# led_4x6_board.net
KiCad netlist of a schematic drawn in EAGLE
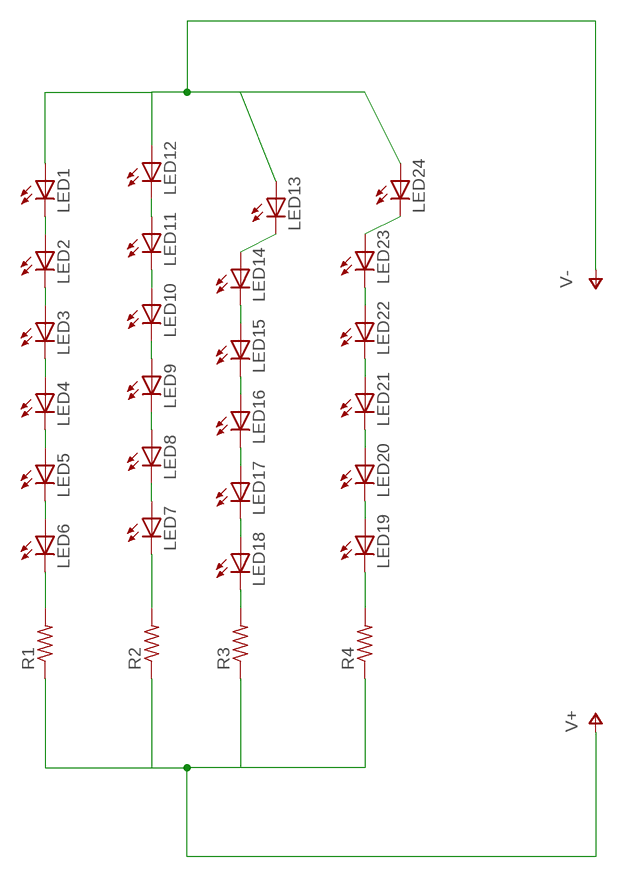
[diagram p0: schematic, sheet 1]

(export (version "E")
  (design (tool "Eeschema 10.0.6"))
  (components
    (comp (ref "LED1")
      (value "LEDLZR181")
      (footprint "eagle-import:LZR181")
      (libsource (lib "eagle-import") (part "LEDLZR181"))
    )
    (comp (ref "LED2")
      (value "LEDLZR181")
      (footprint "eagle-import:LZR181")
      (libsource (lib "eagle-import") (part "LEDLZR181"))
    )
    (comp (ref "LED3")
      (value "LEDLZR181")
      (footprint "eagle-import:LZR181")
      (libsource (lib "eagle-import") (part "LEDLZR181"))
    )
    (comp (ref "LED4")
      (value "LEDLZR181")
      (footprint "eagle-import:LZR181")
      (libsource (lib "eagle-import") (part "LEDLZR181"))
    )
    (comp (ref "LED5")
      (value "LEDLZR181")
      (footprint "eagle-import:LZR181")
      (libsource (lib "eagle-import") (part "LEDLZR181"))
    )
    (comp (ref "LED6")
      (value "LEDLZR181")
      (footprint "eagle-import:LZR181")
      (libsource (lib "eagle-import") (part "LEDLZR181"))
    )
    (comp (ref "LED7")
      (value "LEDLZR181")
      (footprint "eagle-import:LZR181")
      (libsource (lib "eagle-import") (part "LEDLZR181"))
    )
    (comp (ref "LED8")
      (value "LEDLZR181")
      (footprint "eagle-import:LZR181")
      (libsource (lib "eagle-import") (part "LEDLZR181"))
    )
    (comp (ref "LED9")
      (value "LEDLZR181")
      (footprint "eagle-import:LZR181")
      (libsource (lib "eagle-import") (part "LEDLZR181"))
    )
    (comp (ref "LED10")
      (value "LEDLZR181")
      (footprint "eagle-import:LZR181")
      (libsource (lib "eagle-import") (part "LEDLZR181"))
    )
    (comp (ref "LED11")
      (value "LEDLZR181")
      (footprint "eagle-import:LZR181")
      (libsource (lib "eagle-import") (part "LEDLZR181"))
    )
    (comp (ref "LED12")
      (value "LEDLZR181")
      (footprint "eagle-import:LZR181")
      (libsource (lib "eagle-import") (part "LEDLZR181"))
    )
    (comp (ref "LED13")
      (value "LEDLZR181")
      (footprint "eagle-import:LZR181")
      (libsource (lib "eagle-import") (part "LEDLZR181"))
    )
    (comp (ref "LED14")
      (value "LEDLZR181")
      (footprint "eagle-import:LZR181")
      (libsource (lib "eagle-import") (part "LEDLZR181"))
    )
    (comp (ref "LED15")
      (value "LEDLZR181")
      (footprint "eagle-import:LZR181")
      (libsource (lib "eagle-import") (part "LEDLZR181"))
    )
    (comp (ref "LED16")
      (value "LEDLZR181")
      (footprint "eagle-import:LZR181")
      (libsource (lib "eagle-import") (part "LEDLZR181"))
    )
    (comp (ref "LED17")
      (value "LEDLZR181")
      (footprint "eagle-import:LZR181")
      (libsource (lib "eagle-import") (part "LEDLZR181"))
    )
    (comp (ref "LED18")
      (value "LEDLZR181")
      (footprint "eagle-import:LZR181")
      (libsource (lib "eagle-import") (part "LEDLZR181"))
    )
    (comp (ref "LED19")
      (value "LEDLZR181")
      (footprint "eagle-import:LZR181")
      (libsource (lib "eagle-import") (part "LEDLZR181"))
    )
    (comp (ref "LED20")
      (value "LEDLZR181")
      (footprint "eagle-import:LZR181")
      (libsource (lib "eagle-import") (part "LEDLZR181"))
    )
    (comp (ref "LED21")
      (value "LEDLZR181")
      (footprint "eagle-import:LZR181")
      (libsource (lib "eagle-import") (part "LEDLZR181"))
    )
    (comp (ref "LED22")
      (value "LEDLZR181")
      (footprint "eagle-import:LZR181")
      (libsource (lib "eagle-import") (part "LEDLZR181"))
    )
    (comp (ref "LED23")
      (value "LEDLZR181")
      (footprint "eagle-import:LZR181")
      (libsource (lib "eagle-import") (part "LEDLZR181"))
    )
    (comp (ref "LED24")
      (value "LEDLZR181")
      (footprint "eagle-import:LZR181")
      (libsource (lib "eagle-import") (part "LEDLZR181"))
    )
    (comp (ref "R1")
      (value "R-US_V234/12")
      (footprint "eagle-import:V234_12")
      (libsource (lib "eagle-import") (part "R-US_V234/12"))
    )
    (comp (ref "R2")
      (value "R-US_V234/12")
      (footprint "eagle-import:V234_12")
      (libsource (lib "eagle-import") (part "R-US_V234/12"))
    )
    (comp (ref "R3")
      (value "R-US_V234/12")
      (footprint "eagle-import:V234_12")
      (libsource (lib "eagle-import") (part "R-US_V234/12"))
    )
    (comp (ref "R4")
      (value "R-US_V234/12")
      (footprint "eagle-import:V234_12")
      (libsource (lib "eagle-import") (part "R-US_V234/12"))
    )
  )
  (nets
    (net (code "1") (name "Net-(LED1-C)") (class "Default")
      (node (ref "LED1") (pin "K") (pinfunction "C_K") (pintype "passive"))
      (node (ref "LED2") (pin "A") (pinfunction "A_A") (pintype "passive"))
    )
    (net (code "2") (name "Net-(LED2-C)") (class "Default")
      (node (ref "LED2") (pin "K") (pinfunction "C_K") (pintype "passive"))
      (node (ref "LED3") (pin "A") (pinfunction "A_A") (pintype "passive"))
    )
    (net (code "3") (name "Net-(LED3-C)") (class "Default")
      (node (ref "LED3") (pin "K") (pinfunction "C_K") (pintype "passive"))
      (node (ref "LED4") (pin "A") (pinfunction "A_A") (pintype "passive"))
    )
    (net (code "4") (name "Net-(LED4-C)") (class "Default")
      (node (ref "LED4") (pin "K") (pinfunction "C_K") (pintype "passive"))
      (node (ref "LED5") (pin "A") (pinfunction "A_A") (pintype "passive"))
    )
    (net (code "5") (name "Net-(LED5-C)") (class "Default")
      (node (ref "LED5") (pin "K") (pinfunction "C_K") (pintype "passive"))
      (node (ref "LED6") (pin "A") (pinfunction "A_A") (pintype "passive"))
    )
    (net (code "6") (name "Net-(LED6-C)") (class "Default")
      (node (ref "LED6") (pin "K") (pinfunction "C_K") (pintype "passive"))
      (node (ref "R1") (pin "2") (pinfunction "2_2") (pintype "passive"))
    )
    (net (code "7") (name "Net-(LED7-C)") (class "Default")
      (node (ref "LED7") (pin "K") (pinfunction "C_K") (pintype "passive"))
      (node (ref "R2") (pin "2") (pinfunction "2_2") (pintype "passive"))
    )
    (net (code "8") (name "Net-(LED8-C)") (class "Default")
      (node (ref "LED7") (pin "A") (pinfunction "A_A") (pintype "passive"))
      (node (ref "LED8") (pin "K") (pinfunction "C_K") (pintype "passive"))
    )
    (net (code "9") (name "Net-(LED9-C)") (class "Default")
      (node (ref "LED8") (pin "A") (pinfunction "A_A") (pintype "passive"))
      (node (ref "LED9") (pin "K") (pinfunction "C_K") (pintype "passive"))
    )
    (net (code "10") (name "Net-(LED10-C)") (class "Default")
      (node (ref "LED10") (pin "K") (pinfunction "C_K") (pintype "passive"))
      (node (ref "LED9") (pin "A") (pinfunction "A_A") (pintype "passive"))
    )
    (net (code "11") (name "Net-(LED11-C)") (class "Default")
      (node (ref "LED10") (pin "A") (pinfunction "A_A") (pintype "passive"))
      (node (ref "LED11") (pin "K") (pinfunction "C_K") (pintype "passive"))
    )
    (net (code "12") (name "Net-(LED12-C)") (class "Default")
      (node (ref "LED11") (pin "A") (pinfunction "A_A") (pintype "passive"))
      (node (ref "LED12") (pin "K") (pinfunction "C_K") (pintype "passive"))
    )
    (net (code "13") (name "Net-(LED13-C)") (class "Default")
      (node (ref "LED13") (pin "K") (pinfunction "C_K") (pintype "passive"))
      (node (ref "LED14") (pin "A") (pinfunction "A_A") (pintype "passive"))
    )
    (net (code "14") (name "Net-(LED14-C)") (class "Default")
      (node (ref "LED14") (pin "K") (pinfunction "C_K") (pintype "passive"))
      (node (ref "LED15") (pin "A") (pinfunction "A_A") (pintype "passive"))
    )
    (net (code "15") (name "Net-(LED15-C)") (class "Default")
      (node (ref "LED15") (pin "K") (pinfunction "C_K") (pintype "passive"))
      (node (ref "LED16") (pin "A") (pinfunction "A_A") (pintype "passive"))
    )
    (net (code "16") (name "Net-(LED16-C)") (class "Default")
      (node (ref "LED16") (pin "K") (pinfunction "C_K") (pintype "passive"))
      (node (ref "LED17") (pin "A") (pinfunction "A_A") (pintype "passive"))
    )
    (net (code "17") (name "Net-(LED17-C)") (class "Default")
      (node (ref "LED17") (pin "K") (pinfunction "C_K") (pintype "passive"))
      (node (ref "LED18") (pin "A") (pinfunction "A_A") (pintype "passive"))
    )
    (net (code "18") (name "Net-(LED18-C)") (class "Default")
      (node (ref "LED18") (pin "K") (pinfunction "C_K") (pintype "passive"))
      (node (ref "R3") (pin "2") (pinfunction "2_2") (pintype "passive"))
    )
    (net (code "19") (name "Net-(LED19-C)") (class "Default")
      (node (ref "LED19") (pin "K") (pinfunction "C_K") (pintype "passive"))
      (node (ref "R4") (pin "2") (pinfunction "2_2") (pintype "passive"))
    )
    (net (code "20") (name "Net-(LED20-C)") (class "Default")
      (node (ref "LED19") (pin "A") (pinfunction "A_A") (pintype "passive"))
      (node (ref "LED20") (pin "K") (pinfunction "C_K") (pintype "passive"))
    )
    (net (code "21") (name "Net-(LED21-C)") (class "Default")
      (node (ref "LED20") (pin "A") (pinfunction "A_A") (pintype "passive"))
      (node (ref "LED21") (pin "K") (pinfunction "C_K") (pintype "passive"))
    )
    (net (code "22") (name "Net-(LED22-C)") (class "Default")
      (node (ref "LED21") (pin "A") (pinfunction "A_A") (pintype "passive"))
      (node (ref "LED22") (pin "K") (pinfunction "C_K") (pintype "passive"))
    )
    (net (code "23") (name "Net-(LED23-C)") (class "Default")
      (node (ref "LED22") (pin "A") (pinfunction "A_A") (pintype "passive"))
      (node (ref "LED23") (pin "K") (pinfunction "C_K") (pintype "passive"))
    )
    (net (code "24") (name "Net-(LED24-C)") (class "Default")
      (node (ref "LED23") (pin "A") (pinfunction "A_A") (pintype "passive"))
      (node (ref "LED24") (pin "K") (pinfunction "C_K") (pintype "passive"))
    )
    (net (code "25") (name "V+") (class "Default")
      (node (ref "R1") (pin "1") (pinfunction "1_1") (pintype "passive"))
      (node (ref "R2") (pin "1") (pinfunction "1_1") (pintype "passive"))
      (node (ref "R3") (pin "1") (pinfunction "1_1") (pintype "passive"))
      (node (ref "R4") (pin "1") (pinfunction "1_1") (pintype "passive"))
    )
    (net (code "26") (name "V-") (class "Default")
      (node (ref "LED1") (pin "A") (pinfunction "A_A") (pintype "passive"))
      (node (ref "LED12") (pin "A") (pinfunction "A_A") (pintype "passive"))
      (node (ref "LED13") (pin "A") (pinfunction "A_A") (pintype "passive"))
      (node (ref "LED24") (pin "A") (pinfunction "A_A") (pintype "passive"))
    )
  )
)
